# design.net
KiCad netlist of a schematic drawn in Altium Designer
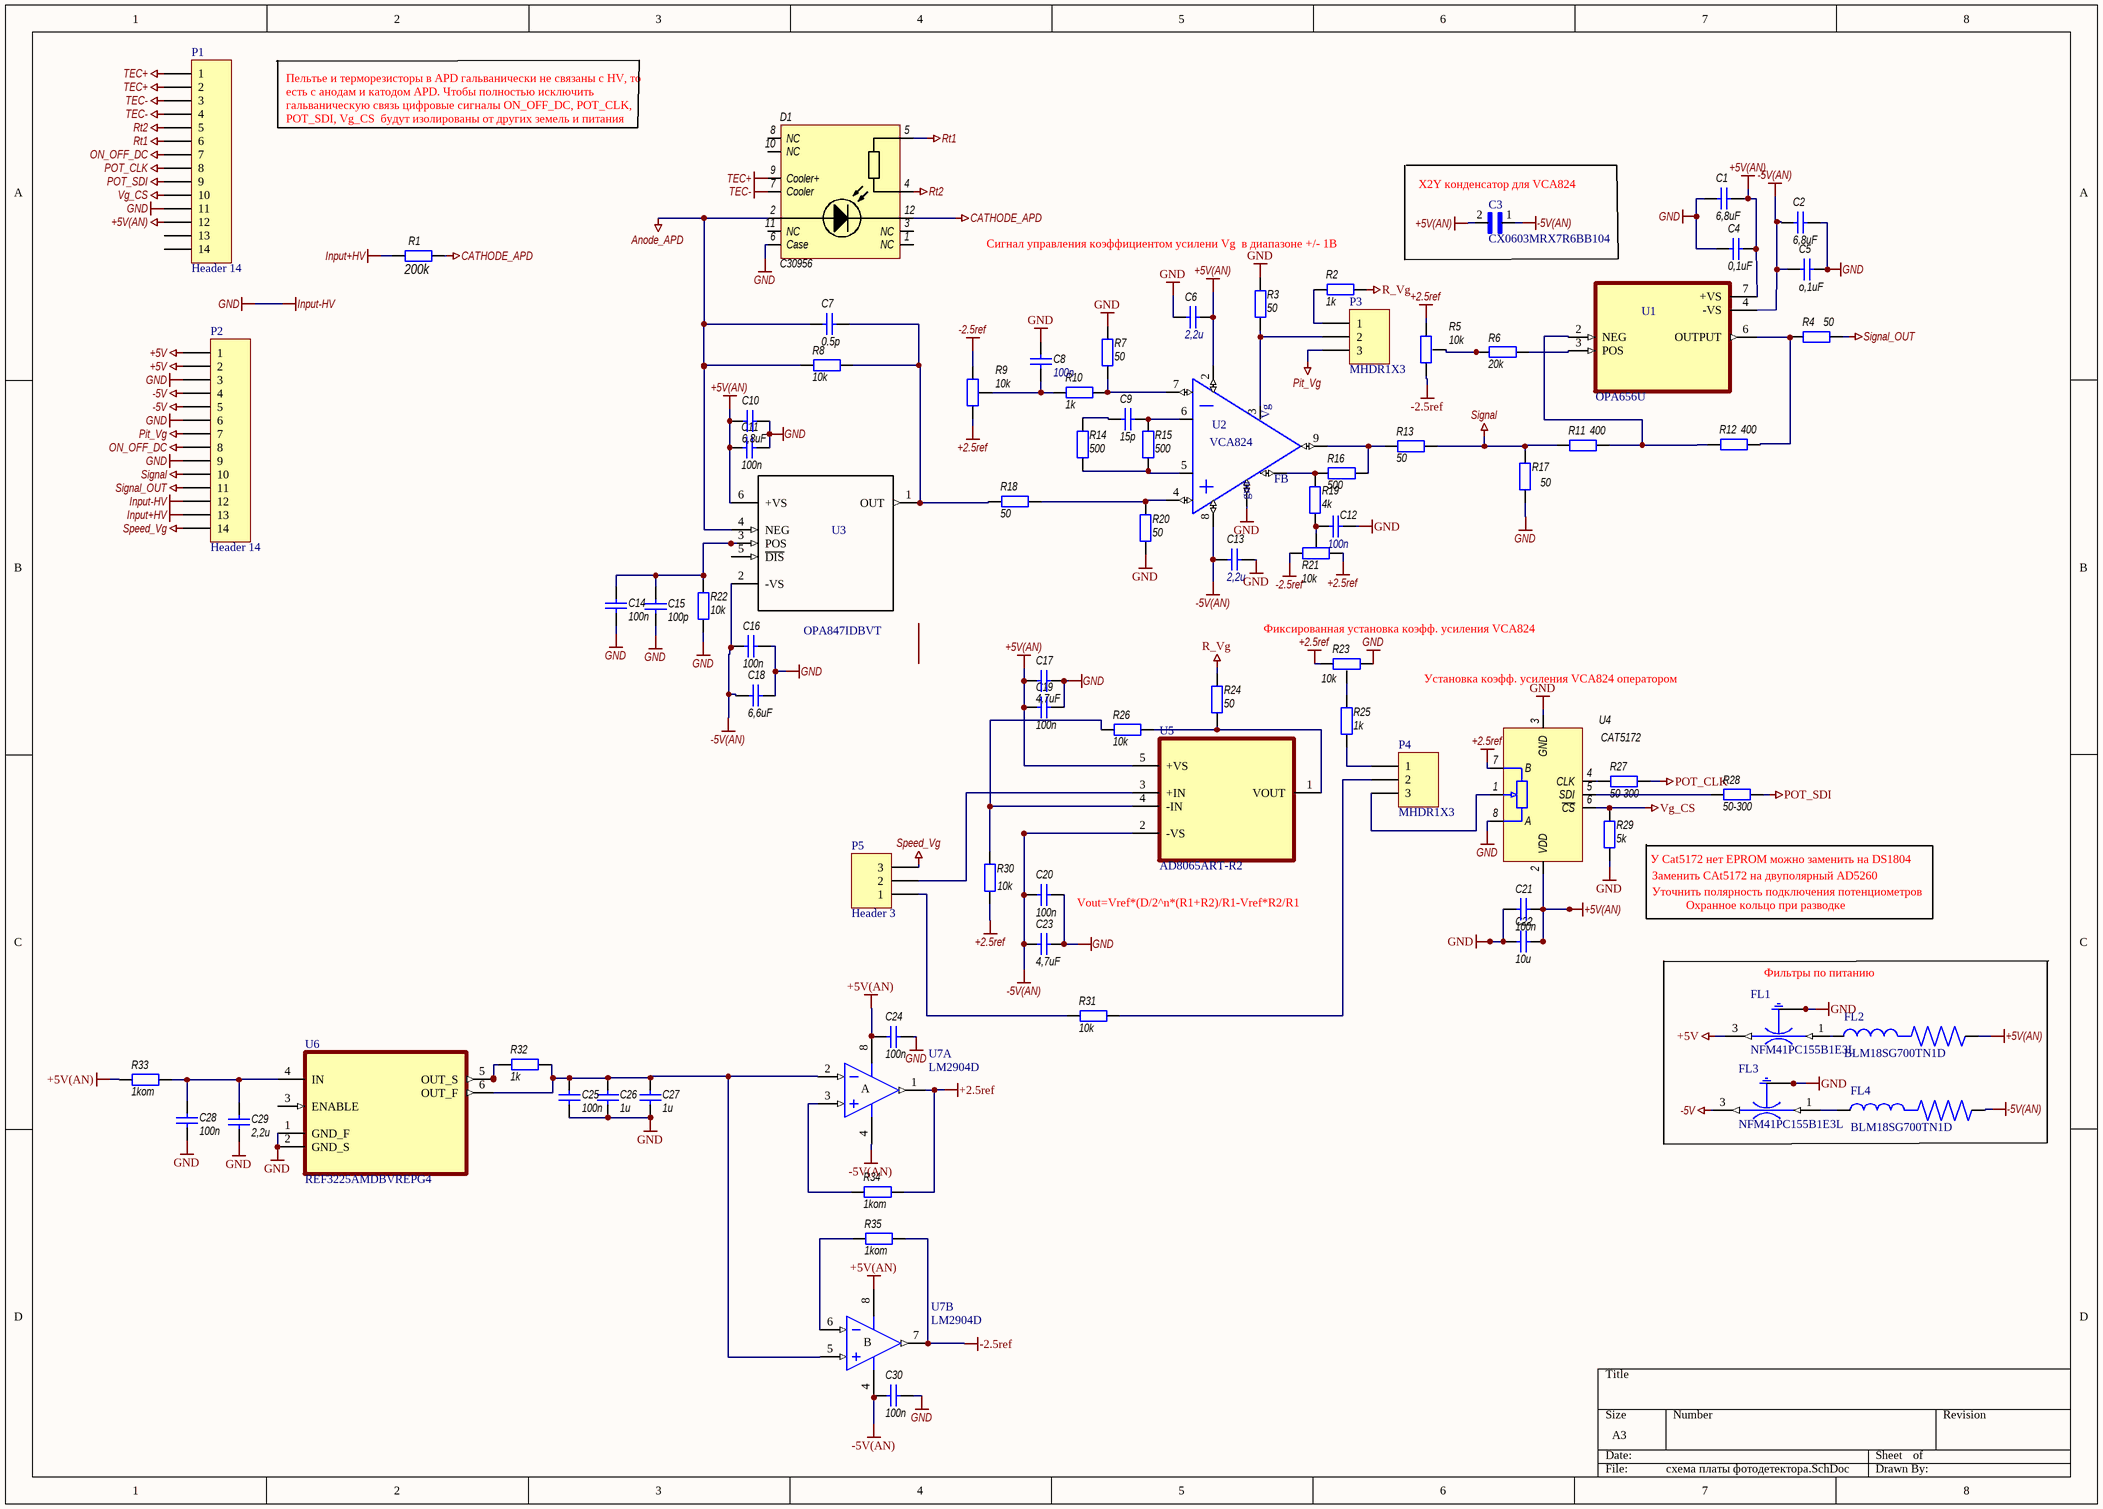
[diagram p0: схема платы фотодетектора.SchDoc]

(export (version "E")
  (design (tool "Eeschema 10.0.6"))
  (components
    (comp (ref "C1") (value "6,8uF") (footprint "0603") (libsource (lib "my-lib") (part "_capacitor")))
    (comp (ref "C2") (value "6,8uF") (footprint "0603") (libsource (lib "my-lib") (part "_capacitor")))
    (comp (ref "C3")
      (value "CX0603MRX7R6BB104")
      (footprint "CAPC1608X90")
      (description "0.1ÂµF Â±20% 10V Ceramic Capacitor X7R 0603 (1608 Metric)")
      (fields (field (name "MF") "Yageo"))
      (libsource (lib "CX0603MRX7R6BB104") (part "CX0603MRX7R6BB104"))
    )
    (comp (ref "C4") (value "0,1uF") (footprint "0603") (libsource (lib "my-lib") (part "_capacitor")))
    (comp (ref "C5") (value "o,1uF") (footprint "0603") (libsource (lib "my-lib") (part "_capacitor")))
    (comp (ref "C6") (value "2,2u") (footprint "0603") (libsource (lib "my-lib") (part "_capacitor")))
    (comp (ref "C7") (value "0.5p") (footprint "0603") (libsource (lib "my-lib") (part "_capacitor")))
    (comp (ref "C8") (value "100n") (footprint "0603") (libsource (lib "my-lib") (part "_capacitor")))
    (comp (ref "C9") (value "15p") (footprint "0603") (libsource (lib "my-lib") (part "_capacitor")))
    (comp (ref "C10") (value "6,8uF") (footprint "0603") (libsource (lib "my-lib") (part "_capacitor")))
    (comp (ref "C11") (value "100n") (footprint "0603") (libsource (lib "my-lib") (part "_capacitor")))
    (comp (ref "C12") (value "100n") (footprint "0603") (libsource (lib "my-lib") (part "_capacitor")))
    (comp (ref "C13") (value "2,2u") (footprint "0603") (libsource (lib "my-lib") (part "_capacitor")))
    (comp (ref "C14") (value "100n") (footprint "0603") (libsource (lib "my-lib") (part "_capacitor")))
    (comp (ref "C15") (value "100p") (footprint "0603") (libsource (lib "my-lib") (part "_capacitor")))
    (comp (ref "C16") (value "100n") (footprint "0603") (libsource (lib "my-lib") (part "_capacitor")))
    (comp (ref "C17") (value "4,7uF") (footprint "0603") (libsource (lib "my-lib") (part "_capacitor")))
    (comp (ref "C18") (value "6,6uF") (footprint "0603") (libsource (lib "my-lib") (part "_capacitor")))
    (comp (ref "C19") (value "100n") (footprint "0603") (libsource (lib "my-lib") (part "_capacitor")))
    (comp (ref "C20") (value "100n") (footprint "0603") (libsource (lib "my-lib") (part "_capacitor")))
    (comp (ref "C21") (value "100n") (footprint "0603") (libsource (lib "my-lib") (part "_capacitor")))
    (comp (ref "C22") (value "10u") (footprint "0603") (libsource (lib "my-lib") (part "_capacitor")))
    (comp (ref "C23") (value "4,7uF") (footprint "0603") (libsource (lib "my-lib") (part "_capacitor")))
    (comp (ref "C24") (value "100n") (footprint "0603") (libsource (lib "my-lib") (part "_capacitor")))
    (comp (ref "C25") (value "100n") (footprint "0603") (libsource (lib "my-lib") (part "_capacitor")))
    (comp (ref "C26") (value "1u") (footprint "0603") (libsource (lib "pcb2") (part "_capacitor")))
    (comp (ref "C27") (value "1u") (footprint "0603") (libsource (lib "pcb2") (part "_capacitor")))
    (comp (ref "C28") (value "100n") (footprint "0603") (libsource (lib "pcb2") (part "_capacitor")))
    (comp (ref "C29") (value "2,2u") (footprint "0603") (libsource (lib "pcb2") (part "_capacitor")))
    (comp (ref "C30") (value "100n") (footprint "0603") (libsource (lib "my-lib") (part "_capacitor")))
    (comp (ref "D1")
      (value "C30956")
      (footprint "C30659")
      (description "ADP_Diod")
      (libsource (lib "my-lib") (part "C30956"))
    )
    (comp (ref "FL1")
      (value "NFM41PC155B1E3L")
      (footprint "FIL_NFM41PC155B1E3L")
      (fields (field (name "MF") "Murata"))
      (libsource (lib "NFM41PC155B1E3L") (part "NFM41PC155B1E3L"))
    )
    (comp (ref "FL2")
      (value "BLM18SG700TN1D")
      (footprint "BEADC2012X105N")
      (fields (field (name "MF") "Murata") (field (name "MP") "BLM21SP111SN1D"))
      (libsource (lib "BLM21SP111SN1D") (part "BLM21SP111SN1D"))
    )
    (comp (ref "FL3")
      (value "NFM41PC155B1E3L")
      (footprint "FIL_NFM41PC155B1E3L")
      (fields (field (name "MF") "Murata"))
      (libsource (lib "NFM41PC155B1E3L") (part "NFM41PC155B1E3L"))
    )
    (comp (ref "FL4")
      (value "BLM18SG700TN1D")
      (footprint "BEADC2012X105N")
      (fields (field (name "MF") "Murata") (field (name "MP") "BLM21SP111SN1D"))
      (libsource (lib "BLM21SP111SN1D") (part "BLM21SP111SN1D"))
    )
    (comp (ref "P1")
      (value "Header 14")
      (footprint "HDR1X14")
      (description "Header, 14-Pin")
      (fields (field (name "PUBLISHER") "Altium Limited"))
      (libsource (lib "Miscellaneous Connectors") (part "Header 14"))
    )
    (comp (ref "P2")
      (value "Header 14")
      (footprint "HDR1X14")
      (description "Header, 14-Pin")
      (fields (field (name "PUBLISHER") "Altium Limited"))
      (libsource (lib "Miscellaneous Connectors") (part "Header 14"))
    )
    (comp (ref "P3")
      (value "MHDR1X3")
      (footprint "HDR1X3")
      (description "Header, 3-Pin")
      (fields (field (name "PUBLISHER") "Altium Limited"))
      (libsource (lib "Miscellaneous Connectors") (part "MHDR1X3"))
    )
    (comp (ref "P4")
      (value "MHDR1X3")
      (footprint "HDR1X3")
      (description "Header, 3-Pin")
      (fields (field (name "PUBLISHER") "Altium Limited"))
      (libsource (lib "Miscellaneous Connectors") (part "MHDR1X3"))
    )
    (comp (ref "P5")
      (value "Header 3")
      (footprint "HDR1X3")
      (description "Header, 3-Pin")
      (fields (field (name "PUBLISHER") "Altium Limited"))
      (libsource (lib "Miscellaneous Connectors") (part "Header 3"))
    )
    (comp (ref "R1")
      (value "200k")
      (footprint "0603")
      (fields (field (name "Comment") "CHV1206"))
      (libsource (lib "my-lib") (part "_resistor"))
    )
    (comp (ref "R2") (value "1k") (footprint "0603") (libsource (lib "my-lib") (part "_resistor")))
    (comp (ref "R3") (value "50") (footprint "0603") (libsource (lib "my-lib") (part "_resistor")))
    (comp (ref "R4") (value "50") (footprint "0603") (libsource (lib "my-lib") (part "_resistor")))
    (comp (ref "R5")
      (value "10k")
      (footprint "respotBourns")
      (description "3224J-1-103")
      (libsource (lib "my-lib") (part "_resistor_pot"))
    )
    (comp (ref "R6") (value "20k") (footprint "0603") (libsource (lib "my-lib") (part "_resistor")))
    (comp (ref "R7") (value "50") (footprint "0603") (libsource (lib "my-lib") (part "_resistor")))
    (comp (ref "R8") (value "10k") (footprint "0603") (libsource (lib "my-lib") (part "_resistor")))
    (comp (ref "R9")
      (value "10k")
      (footprint "respotBourns")
      (description "3224J-1-103")
      (libsource (lib "my-lib") (part "_resistor_pot"))
    )
    (comp (ref "R10") (value "1k") (footprint "0603") (libsource (lib "my-lib") (part "_resistor")))
    (comp (ref "R11") (value "400") (footprint "0603") (libsource (lib "my-lib") (part "_resistor")))
    (comp (ref "R12") (value "400") (footprint "0603") (libsource (lib "my-lib") (part "_resistor")))
    (comp (ref "R13") (value "50") (footprint "0603") (libsource (lib "my-lib") (part "_resistor")))
    (comp (ref "R14") (value "500") (footprint "0603") (libsource (lib "my-lib") (part "_resistor")))
    (comp (ref "R15") (value "500") (footprint "0603") (libsource (lib "my-lib") (part "_resistor")))
    (comp (ref "R16") (value "500") (footprint "0603") (libsource (lib "my-lib") (part "_resistor")))
    (comp (ref "R17") (value "50") (footprint "0603") (libsource (lib "my-lib") (part "_resistor")))
    (comp (ref "R18") (value "50") (footprint "0603") (libsource (lib "my-lib") (part "_resistor")))
    (comp (ref "R19") (value "4k") (footprint "0603") (libsource (lib "my-lib") (part "_resistor")))
    (comp (ref "R20") (value "50") (footprint "0603") (libsource (lib "my-lib") (part "_resistor")))
    (comp (ref "R21")
      (value "10k")
      (footprint "respotBourns")
      (description "3224J-1-103")
      (libsource (lib "my-lib") (part "_resistor_pot"))
    )
    (comp (ref "R22") (value "10k") (footprint "0603") (libsource (lib "my-lib") (part "_resistor")))
    (comp (ref "R23")
      (value "10k")
      (footprint "respotBourns")
      (description "3224j-1-103")
      (libsource (lib "my-lib") (part "_resistor_pot"))
    )
    (comp (ref "R24") (value "50") (footprint "0603") (libsource (lib "my-lib") (part "_resistor")))
    (comp (ref "R25") (value "1k") (footprint "0603") (libsource (lib "my-lib") (part "_resistor")))
    (comp (ref "R26") (value "10k") (footprint "0603") (libsource (lib "my-lib") (part "_resistor")))
    (comp (ref "R27") (value "50-300") (footprint "0603") (libsource (lib "my-lib") (part "_resistor")))
    (comp (ref "R28") (value "50-300") (footprint "0603") (libsource (lib "my-lib") (part "_resistor")))
    (comp (ref "R29") (value "5k") (footprint "0603") (libsource (lib "my-lib") (part "_resistor")))
    (comp (ref "R30") (value "10k") (footprint "0603") (libsource (lib "my-lib") (part "_resistor")))
    (comp (ref "R31") (value "10k") (footprint "0603") (libsource (lib "my-lib") (part "_resistor")))
    (comp (ref "R32") (value "1k") (footprint "0603") (libsource (lib "my-lib") (part "_resistor")))
    (comp (ref "R33") (value "1kom") (footprint "0603") (libsource (lib "pcb2") (part "_resistor")))
    (comp (ref "R34") (value "1kom") (footprint "0603") (libsource (lib "pcb2") (part "_resistor")))
    (comp (ref "R35") (value "1kom") (footprint "0603") (libsource (lib "pcb2") (part "_resistor")))
    (comp (ref "U1")
      (value "OPA656U")
      (footprint "SOIC127P599X175-8N")
      (description "Wideband, Unity Gain Stable FET-Input Operational Amplifier")
      (fields (field (name "MF") "Texas Instruments"))
      (libsource (lib "OPA656U") (part "OPA656U"))
    )
    (comp (ref "U2")
      (value "VCA824")
      (footprint "MSOP10")
      (fields (field (name "MF") "Texas Instruments"))
      (libsource (lib "VCA824") (part "VCA824"))
    )
    (comp (ref "U3")
      (value "OPA847IDBVT")
      (footprint "*SOT95P280X145-6N")
      (libsource (lib "OPA847IDBVT") (part "OPA847IDBVT"))
    )
    (comp (ref "U4")
      (value "CAT5172")
      (footprint "SOT238")
      (description "Digital potentiometr 256-position SPI")
      (libsource (lib "my-lib") (part "CAT5172"))
    )
    (comp (ref "U5")
      (value "AD8065ART-R2")
      (footprint "SOT95P290X145-5N")
      (fields (field (name "MF") "Analog Devices"))
      (libsource (lib "AD8065ART-R2") (part "AD8065ART-R2"))
    )
    (comp (ref "U6")
      (value "REF3225AMDBVREPG4")
      (footprint "SOT95P280X145-6N")
      (fields (field (name "MF") "Texas Instruments"))
      (libsource (lib "REF3225AMDBVREPG4") (part "REF3225AMDBVREPG4"))
    )
    (comp (ref "U7")
      (value "LM2904D")
      (footprint "SO8_L")
      (description "Low-Power Dual Operational Amplifier")
      (fields (field (name "PUBLISHER") "Altium Limited"))
      (libsource (lib "ST Operational Amplifier") (part "LM2904D"))
    )
  )
  (nets
    (net (code "1") (name "+2.5ref") (class "Default")
      (node (ref "R21") (pin "3") (pinfunction "3_3") (pintype "passive"))
      (node (ref "R23") (pin "3") (pinfunction "3_3") (pintype "passive"))
      (node (ref "R30") (pin "1") (pinfunction "1_1") (pintype "passive"))
      (node (ref "R34") (pin "1") (pinfunction "1_1") (pintype "passive"))
      (node (ref "R5") (pin "1") (pinfunction "1_1") (pintype "passive"))
      (node (ref "R9") (pin "3") (pinfunction "3_3") (pintype "passive"))
      (node (ref "U4") (pin "7") (pinfunction "B_7") (pintype "passive"))
      (node (ref "U7") (pin "1") (pinfunction "OUT_1") (pintype "output"))
    )
    (net (code "2") (name "+5V") (class "Default")
      (node (ref "FL1") (pin "3") (pinfunction "OUT_3") (pintype "output"))
      (node (ref "P2") (pin "1") (pinfunction "1_1") (pintype "passive"))
      (node (ref "P2") (pin "2") (pinfunction "2_2") (pintype "passive"))
    )
    (net (code "3") (name "+5V(AN)") (class "Default")
      (node (ref "C1") (pin "1") (pinfunction "1_1") (pintype "passive"))
      (node (ref "C10") (pin "1") (pinfunction "1_1") (pintype "passive"))
      (node (ref "C11") (pin "2") (pinfunction "2_2") (pintype "passive"))
      (node (ref "C17") (pin "2") (pinfunction "2_2") (pintype "passive"))
      (node (ref "C19") (pin "2") (pinfunction "2_2") (pintype "passive"))
      (node (ref "C21") (pin "2") (pinfunction "2_2") (pintype "passive"))
      (node (ref "C22") (pin "2") (pinfunction "2_2") (pintype "passive"))
      (node (ref "C24") (pin "2") (pinfunction "2_2") (pintype "passive"))
      (node (ref "C3") (pin "2") (pinfunction "2_2") (pintype "passive"))
      (node (ref "C4") (pin "1") (pinfunction "1_1") (pintype "passive"))
      (node (ref "C6") (pin "1") (pinfunction "1_1") (pintype "passive"))
      (node (ref "FL2") (pin "2") (pinfunction "2_2") (pintype "passive"))
      (node (ref "P1") (pin "12") (pinfunction "12_12") (pintype "passive"))
      (node (ref "R33") (pin "2") (pinfunction "2_2") (pintype "passive"))
      (node (ref "U1") (pin "7") (pinfunction "+VS_7") (pintype "power_in"))
      (node (ref "U2") (pin "2") (pinfunction "V+_2") (pintype "bidirectional"))
      (node (ref "U3") (pin "6") (pinfunction "+VS_6") (pintype "power_in"))
      (node (ref "U4") (pin "2") (pinfunction "VDD_2") (pintype "passive"))
      (node (ref "U5") (pin "5") (pinfunction "+VS_5") (pintype "power_in"))
      (node (ref "U7") (pin "8") (pinfunction "V+_8") (pintype "power_in"))
    )
    (net (code "4") (name "-2.5ref") (class "Default")
      (node (ref "R21") (pin "1") (pinfunction "1_1") (pintype "passive"))
      (node (ref "R35") (pin "1") (pinfunction "1_1") (pintype "passive"))
      (node (ref "R5") (pin "3") (pinfunction "3_3") (pintype "passive"))
      (node (ref "R9") (pin "1") (pinfunction "1_1") (pintype "passive"))
      (node (ref "U7") (pin "7") (pinfunction "OUT_7") (pintype "output"))
    )
    (net (code "5") (name "-5V") (class "Default")
      (node (ref "FL3") (pin "3") (pinfunction "OUT_3") (pintype "output"))
      (node (ref "P2") (pin "4") (pinfunction "4_4") (pintype "passive"))
      (node (ref "P2") (pin "5") (pinfunction "5_5") (pintype "passive"))
    )
    (net (code "6") (name "-5V(AN)") (class "Default")
      (node (ref "C13") (pin "2") (pinfunction "2_2") (pintype "passive"))
      (node (ref "C16") (pin "2") (pinfunction "2_2") (pintype "passive"))
      (node (ref "C18") (pin "1") (pinfunction "1_1") (pintype "passive"))
      (node (ref "C2") (pin "2") (pinfunction "2_2") (pintype "passive"))
      (node (ref "C20") (pin "2") (pinfunction "2_2") (pintype "passive"))
      (node (ref "C23") (pin "2") (pinfunction "2_2") (pintype "passive"))
      (node (ref "C3") (pin "1") (pinfunction "1_1") (pintype "passive"))
      (node (ref "C30") (pin "2") (pinfunction "2_2") (pintype "passive"))
      (node (ref "C5") (pin "2") (pinfunction "2_2") (pintype "passive"))
      (node (ref "FL4") (pin "2") (pinfunction "2_2") (pintype "passive"))
      (node (ref "U1") (pin "4") (pinfunction "-VS_4") (pintype "power_in"))
      (node (ref "U2") (pin "8") (pinfunction "V-_8") (pintype "bidirectional"))
      (node (ref "U3") (pin "2") (pinfunction "-VS_2") (pintype "power_in"))
      (node (ref "U5") (pin "2") (pinfunction "-VS_2") (pintype "power_in"))
      (node (ref "U7") (pin "4") (pinfunction "V-_4") (pintype "power_in"))
    )
    (net (code "7") (name "Anode_APD") (class "Default")
      (node (ref "C7") (pin "2") (pinfunction "2_2") (pintype "passive"))
      (node (ref "D1") (pin "2") (pintype "passive"))
      (node (ref "R8") (pin "1") (pinfunction "1_1") (pintype "passive"))
      (node (ref "U3") (pin "4") (pinfunction "NEG_4") (pintype "input"))
    )
    (net (code "8") (name "CATHODE_APD") (class "Default")
      (node (ref "D1") (pin "12") (pintype "passive"))
      (node (ref "R1") (pin "2") (pinfunction "2_2") (pintype "passive"))
    )
    (net (code "9") (name "GND") (class "Default")
      (node (ref "C1") (pin "2") (pinfunction "2_2") (pintype "passive"))
      (node (ref "C10") (pin "2") (pinfunction "2_2") (pintype "passive"))
      (node (ref "C11") (pin "1") (pinfunction "1_1") (pintype "passive"))
      (node (ref "C12") (pin "1") (pinfunction "1_1") (pintype "passive"))
      (node (ref "C13") (pin "1") (pinfunction "1_1") (pintype "passive"))
      (node (ref "C14") (pin "1") (pinfunction "1_1") (pintype "passive"))
      (node (ref "C15") (pin "2") (pinfunction "2_2") (pintype "passive"))
      (node (ref "C16") (pin "1") (pinfunction "1_1") (pintype "passive"))
      (node (ref "C17") (pin "1") (pinfunction "1_1") (pintype "passive"))
      (node (ref "C18") (pin "2") (pinfunction "2_2") (pintype "passive"))
      (node (ref "C19") (pin "1") (pinfunction "1_1") (pintype "passive"))
      (node (ref "C2") (pin "1") (pinfunction "1_1") (pintype "passive"))
      (node (ref "C20") (pin "1") (pinfunction "1_1") (pintype "passive"))
      (node (ref "C21") (pin "1") (pinfunction "1_1") (pintype "passive"))
      (node (ref "C22") (pin "1") (pinfunction "1_1") (pintype "passive"))
      (node (ref "C23") (pin "1") (pinfunction "1_1") (pintype "passive"))
      (node (ref "C24") (pin "1") (pinfunction "1_1") (pintype "passive"))
      (node (ref "C25") (pin "1") (pinfunction "1_1") (pintype "passive"))
      (node (ref "C26") (pin "1") (pinfunction "1_1") (pintype "passive"))
      (node (ref "C27") (pin "1") (pinfunction "1_1") (pintype "passive"))
      (node (ref "C28") (pin "1") (pinfunction "1_1") (pintype "passive"))
      (node (ref "C29") (pin "1") (pinfunction "1_1") (pintype "passive"))
      (node (ref "C30") (pin "1") (pinfunction "1_1") (pintype "passive"))
      (node (ref "C4") (pin "2") (pinfunction "2_2") (pintype "passive"))
      (node (ref "C5") (pin "1") (pinfunction "1_1") (pintype "passive"))
      (node (ref "C6") (pin "2") (pinfunction "2_2") (pintype "passive"))
      (node (ref "C8") (pin "2") (pinfunction "2_2") (pintype "passive"))
      (node (ref "D1") (pin "6") (pinfunction "Case_6") (pintype "passive"))
      (node (ref "FL1") (pin "2") (pinfunction "GND_2") (pintype "power_in"))
      (node (ref "FL1") (pin "2_1") (pinfunction "GND_2_1") (pintype "power_in"))
      (node (ref "FL1") (pin "2_3") (pinfunction "GND_2_3") (pintype "power_in"))
      (node (ref "FL1") (pin "2_4") (pinfunction "GND_2_4") (pintype "power_in"))
      (node (ref "FL3") (pin "2") (pinfunction "GND_2") (pintype "power_in"))
      (node (ref "FL3") (pin "2_1") (pinfunction "GND_2_1") (pintype "power_in"))
      (node (ref "FL3") (pin "2_3") (pinfunction "GND_2_3") (pintype "power_in"))
      (node (ref "FL3") (pin "2_4") (pinfunction "GND_2_4") (pintype "power_in"))
      (node (ref "P1") (pin "11") (pinfunction "11_11") (pintype "passive"))
      (node (ref "P2") (pin "12") (pinfunction "12_12") (pintype "passive"))
      (node (ref "P2") (pin "3") (pinfunction "3_3") (pintype "passive"))
      (node (ref "P2") (pin "6") (pinfunction "6_6") (pintype "passive"))
      (node (ref "P2") (pin "9") (pinfunction "9_9") (pintype "passive"))
      (node (ref "R17") (pin "1") (pinfunction "1_1") (pintype "passive"))
      (node (ref "R20") (pin "1") (pinfunction "1_1") (pintype "passive"))
      (node (ref "R22") (pin "2") (pinfunction "2_2") (pintype "passive"))
      (node (ref "R23") (pin "1") (pinfunction "1_1") (pintype "passive"))
      (node (ref "R29") (pin "1") (pinfunction "1_1") (pintype "passive"))
      (node (ref "R3") (pin "2") (pinfunction "2_2") (pintype "passive"))
      (node (ref "R7") (pin "2") (pinfunction "2_2") (pintype "passive"))
      (node (ref "U2") (pin "10") (pinfunction "GND_10") (pintype "bidirectional"))
      (node (ref "U4") (pin "3") (pinfunction "GND_3") (pintype "passive"))
      (node (ref "U4") (pin "8") (pinfunction "A_8") (pintype "passive"))
      (node (ref "U6") (pin "1") (pinfunction "GND_F_1") (pintype "passive"))
      (node (ref "U6") (pin "2") (pinfunction "GND_S_2") (pintype "passive"))
    )
    (net (code "10") (name "Input+HV") (class "Default")
      (node (ref "P2") (pin "13") (pinfunction "13_13") (pintype "passive"))
      (node (ref "R1") (pin "1") (pinfunction "1_1") (pintype "passive"))
    )
    (net (code "11") (name "Net-(C8-Pad1)") (class "Default")
      (node (ref "C8") (pin "1") (pinfunction "1_1") (pintype "passive"))
      (node (ref "R10") (pin "1") (pinfunction "1_1") (pintype "passive"))
      (node (ref "R9") (pin "2") (pinfunction "2_2") (pintype "passive"))
    )
    (net (code "12") (name "Net-(C9-Pad2)") (class "Default")
      (node (ref "C9") (pin "2") (pinfunction "2_2") (pintype "passive"))
      (node (ref "R14") (pin "2") (pinfunction "2_2") (pintype "passive"))
    )
    (net (code "13") (name "Net-(C12-Pad2)") (class "Default")
      (node (ref "C12") (pin "2") (pinfunction "2_2") (pintype "passive"))
      (node (ref "R19") (pin "1") (pinfunction "1_1") (pintype "passive"))
      (node (ref "R21") (pin "2") (pinfunction "2_2") (pintype "passive"))
    )
    (net (code "14") (name "Net-(FL1-IN)") (class "Default")
      (node (ref "FL1") (pin "1") (pinfunction "IN_1") (pintype "input"))
      (node (ref "FL2") (pin "1") (pinfunction "1_1") (pintype "passive"))
    )
    (net (code "15") (name "Net-(FL3-IN)") (class "Default")
      (node (ref "FL3") (pin "1") (pinfunction "IN_1") (pintype "input"))
      (node (ref "FL4") (pin "1") (pinfunction "1_1") (pintype "passive"))
    )
    (net (code "16") (name "Net-(P3-Pad1)") (class "Default")
      (node (ref "P3") (pin "1") (pinfunction "1_1") (pintype "passive"))
      (node (ref "R2") (pin "1") (pinfunction "1_1") (pintype "passive"))
    )
    (net (code "17") (name "Net-(P4-Pad1)") (class "Default")
      (node (ref "P4") (pin "1") (pinfunction "1_1") (pintype "passive"))
      (node (ref "R25") (pin "1") (pinfunction "1_1") (pintype "passive"))
    )
    (net (code "18") (name "Net-(P4-Pad2)") (class "Default")
      (node (ref "P4") (pin "2") (pinfunction "2_2") (pintype "passive"))
      (node (ref "R31") (pin "2") (pinfunction "2_2") (pintype "passive"))
    )
    (net (code "19") (name "Net-(P4-Pad3)") (class "Default")
      (node (ref "P4") (pin "3") (pinfunction "3_3") (pintype "passive"))
      (node (ref "U4") (pin "1") (pintype "passive"))
    )
    (net (code "20") (name "Net-(P5-Pad1)") (class "Default")
      (node (ref "P5") (pin "1") (pinfunction "1_1") (pintype "passive"))
      (node (ref "R31") (pin "1") (pinfunction "1_1") (pintype "passive"))
    )
    (net (code "21") (name "Net-(R5-Pad2)") (class "Default")
      (node (ref "R5") (pin "2") (pinfunction "2_2") (pintype "passive"))
      (node (ref "R6") (pin "1") (pinfunction "1_1") (pintype "passive"))
    )
    (net (code "22") (name "Net-(R23-Pad2)") (class "Default")
      (node (ref "R23") (pin "2") (pinfunction "2_2") (pintype "passive"))
      (node (ref "R25") (pin "2") (pinfunction "2_2") (pintype "passive"))
    )
    (net (code "23") (name "Net-(U1-NEG)") (class "Default")
      (node (ref "R11") (pin "2") (pinfunction "2_2") (pintype "passive"))
      (node (ref "R12") (pin "1") (pinfunction "1_1") (pintype "passive"))
      (node (ref "U1") (pin "2") (pinfunction "NEG_2") (pintype "input"))
    )
    (net (code "24") (name "Net-(U1-OUTPUT)") (class "Default")
      (node (ref "R12") (pin "2") (pinfunction "2_2") (pintype "passive"))
      (node (ref "R4") (pin "1") (pinfunction "1_1") (pintype "passive"))
      (node (ref "U1") (pin "6") (pinfunction "OUTPUT_6") (pintype "output"))
    )
    (net (code "25") (name "Net-(U1-POS)") (class "Default")
      (node (ref "R6") (pin "2") (pinfunction "2_2") (pintype "passive"))
      (node (ref "U1") (pin "3") (pinfunction "POS_3") (pintype "input"))
    )
    (net (code "26") (name "Net-(U2-FB)") (class "Default")
      (node (ref "R16") (pin "1") (pinfunction "1_1") (pintype "passive"))
      (node (ref "R19") (pin "2") (pinfunction "2_2") (pintype "passive"))
      (node (ref "U2") (pin "1") (pinfunction "FB_1") (pintype "bidirectional"))
    )
    (net (code "27") (name "Net-(U2-IN+)") (class "Default")
      (node (ref "R18") (pin "2") (pinfunction "2_2") (pintype "passive"))
      (node (ref "R20") (pin "2") (pinfunction "2_2") (pintype "passive"))
      (node (ref "U2") (pin "4") (pinfunction "IN+_4") (pintype "bidirectional"))
    )
    (net (code "28") (name "Net-(U2-IN-)") (class "Default")
      (node (ref "R10") (pin "2") (pinfunction "2_2") (pintype "passive"))
      (node (ref "R7") (pin "1") (pinfunction "1_1") (pintype "passive"))
      (node (ref "U2") (pin "7") (pinfunction "IN-_7") (pintype "bidirectional"))
    )
    (net (code "29") (name "Net-(U2-OUT)") (class "Default")
      (node (ref "R13") (pin "1") (pinfunction "1_1") (pintype "passive"))
      (node (ref "R16") (pin "2") (pinfunction "2_2") (pintype "passive"))
      (node (ref "U2") (pin "9") (pinfunction "OUT_9") (pintype "bidirectional"))
    )
    (net (code "30") (name "Net-(U2-RG+)") (class "Default")
      (node (ref "R14") (pin "1") (pinfunction "1_1") (pintype "passive"))
      (node (ref "R15") (pin "1") (pinfunction "1_1") (pintype "passive"))
      (node (ref "U2") (pin "5") (pinfunction "RG+_5") (pintype "bidirectional"))
    )
    (net (code "31") (name "Net-(U2-RG-)") (class "Default")
      (node (ref "C9") (pin "1") (pinfunction "1_1") (pintype "passive"))
      (node (ref "R15") (pin "2") (pinfunction "2_2") (pintype "passive"))
      (node (ref "U2") (pin "6") (pinfunction "RG-_6") (pintype "bidirectional"))
    )
    (net (code "32") (name "Net-(U2-VG)") (class "Default")
      (node (ref "P3") (pin "2") (pinfunction "2_2") (pintype "passive"))
      (node (ref "R3") (pin "1") (pinfunction "1_1") (pintype "passive"))
      (node (ref "U2") (pin "3") (pinfunction "VG_3") (pintype "bidirectional"))
    )
    (net (code "33") (name "Net-(U3-OUT)") (class "Default")
      (node (ref "C7") (pin "1") (pinfunction "1_1") (pintype "passive"))
      (node (ref "R18") (pin "1") (pinfunction "1_1") (pintype "passive"))
      (node (ref "R8") (pin "2") (pinfunction "2_2") (pintype "passive"))
      (node (ref "U3") (pin "1") (pinfunction "OUT_1") (pintype "output"))
    )
    (net (code "34") (name "Net-(U3-POS)") (class "Default")
      (node (ref "C14") (pin "2") (pinfunction "2_2") (pintype "passive"))
      (node (ref "C15") (pin "1") (pinfunction "1_1") (pintype "passive"))
      (node (ref "R22") (pin "1") (pinfunction "1_1") (pintype "passive"))
      (node (ref "U3") (pin "3") (pinfunction "POS_3") (pintype "input"))
    )
    (net (code "35") (name "Net-(U4-CLK)") (class "Default")
      (node (ref "R27") (pin "1") (pinfunction "1_1") (pintype "passive"))
      (node (ref "U4") (pin "4") (pinfunction "CLK_4") (pintype "passive"))
    )
    (net (code "36") (name "Net-(U4-SDI)") (class "Default")
      (node (ref "R28") (pin "1") (pinfunction "1_1") (pintype "passive"))
      (node (ref "U4") (pin "5") (pinfunction "SDI_5") (pintype "passive"))
    )
    (net (code "37") (name "Net-(U5-+IN)") (class "Default")
      (node (ref "P5") (pin "2") (pinfunction "2_2") (pintype "passive"))
      (node (ref "U5") (pin "3") (pinfunction "+IN_3") (pintype "passive"))
    )
    (net (code "38") (name "Net-(U5--IN)") (class "Default")
      (node (ref "R26") (pin "1") (pinfunction "1_1") (pintype "passive"))
      (node (ref "R30") (pin "2") (pinfunction "2_2") (pintype "passive"))
      (node (ref "U5") (pin "4") (pinfunction "-IN_4") (pintype "passive"))
    )
    (net (code "39") (name "Net-(U5-VOUT)") (class "Default")
      (node (ref "R24") (pin "1") (pinfunction "1_1") (pintype "passive"))
      (node (ref "R26") (pin "2") (pinfunction "2_2") (pintype "passive"))
      (node (ref "U5") (pin "1") (pinfunction "VOUT_1") (pintype "passive"))
    )
    (net (code "40") (name "Net-(U6-IN)") (class "Default")
      (node (ref "C28") (pin "2") (pinfunction "2_2") (pintype "passive"))
      (node (ref "C29") (pin "2") (pinfunction "2_2") (pintype "passive"))
      (node (ref "R33") (pin "1") (pinfunction "1_1") (pintype "passive"))
      (node (ref "U6") (pin "4") (pinfunction "IN_4") (pintype "power_in"))
    )
    (net (code "41") (name "Net-(U6-OUT_F)") (class "Default")
      (node (ref "C25") (pin "2") (pinfunction "2_2") (pintype "passive"))
      (node (ref "C26") (pin "2") (pinfunction "2_2") (pintype "passive"))
      (node (ref "C27") (pin "2") (pinfunction "2_2") (pintype "passive"))
      (node (ref "R32") (pin "2") (pinfunction "2_2") (pintype "passive"))
      (node (ref "U6") (pin "6") (pinfunction "OUT_F_6") (pintype "output"))
      (node (ref "U7") (pin "2") (pinfunction "IN-_2") (pintype "input"))
      (node (ref "U7") (pin "5") (pinfunction "IN+_5") (pintype "input"))
    )
    (net (code "42") (name "Net-(U6-OUT_S)") (class "Default")
      (node (ref "R32") (pin "1") (pinfunction "1_1") (pintype "passive"))
      (node (ref "U6") (pin "5") (pinfunction "OUT_S_5") (pintype "output"))
    )
    (net (code "43") (name "Net-(U7A-IN+)") (class "Default")
      (node (ref "R34") (pin "2") (pinfunction "2_2") (pintype "passive"))
      (node (ref "U7") (pin "3") (pinfunction "IN+_3") (pintype "input"))
    )
    (net (code "44") (name "Net-(U7B-IN-)") (class "Default")
      (node (ref "R35") (pin "2") (pinfunction "2_2") (pintype "passive"))
      (node (ref "U7") (pin "6") (pinfunction "IN-_6") (pintype "input"))
    )
    (net (code "45") (name "ON_OFF_DC") (class "Default")
      (node (ref "P1") (pin "7") (pinfunction "7_7") (pintype "passive"))
      (node (ref "P2") (pin "8") (pinfunction "8_8") (pintype "passive"))
    )
    (net (code "46") (name "POT_CLK") (class "Default")
      (node (ref "P1") (pin "8") (pinfunction "8_8") (pintype "passive"))
      (node (ref "R27") (pin "2") (pinfunction "2_2") (pintype "passive"))
    )
    (net (code "47") (name "POT_SDI") (class "Default")
      (node (ref "P1") (pin "9") (pinfunction "9_9") (pintype "passive"))
      (node (ref "R28") (pin "2") (pinfunction "2_2") (pintype "passive"))
    )
    (net (code "48") (name "Pit_Vg") (class "Default")
      (node (ref "P2") (pin "7") (pinfunction "7_7") (pintype "passive"))
      (node (ref "P3") (pin "3") (pinfunction "3_3") (pintype "passive"))
    )
    (net (code "49") (name "R_Vg") (class "Default")
      (node (ref "R2") (pin "2") (pinfunction "2_2") (pintype "passive"))
      (node (ref "R24") (pin "2") (pinfunction "2_2") (pintype "passive"))
    )
    (net (code "50") (name "Rt1") (class "Default")
      (node (ref "D1") (pin "5") (pintype "passive"))
      (node (ref "P1") (pin "6") (pinfunction "6_6") (pintype "passive"))
    )
    (net (code "51") (name "Rt2") (class "Default")
      (node (ref "D1") (pin "4") (pintype "passive"))
      (node (ref "P1") (pin "5") (pinfunction "5_5") (pintype "passive"))
    )
    (net (code "52") (name "Signal") (class "Default")
      (node (ref "P2") (pin "10") (pinfunction "10_10") (pintype "passive"))
      (node (ref "R11") (pin "1") (pinfunction "1_1") (pintype "passive"))
      (node (ref "R13") (pin "2") (pinfunction "2_2") (pintype "passive"))
      (node (ref "R17") (pin "2") (pinfunction "2_2") (pintype "passive"))
    )
    (net (code "53") (name "Signal_OUT") (class "Default")
      (node (ref "P2") (pin "11") (pinfunction "11_11") (pintype "passive"))
      (node (ref "R4") (pin "2") (pinfunction "2_2") (pintype "passive"))
    )
    (net (code "54") (name "Speed_Vg") (class "Default")
      (node (ref "P2") (pin "14") (pinfunction "14_14") (pintype "passive"))
      (node (ref "P5") (pin "3") (pinfunction "3_3") (pintype "passive"))
    )
    (net (code "55") (name "TEC+") (class "Default")
      (node (ref "D1") (pin "9") (pinfunction "Cooler+_9") (pintype "passive"))
      (node (ref "P1") (pin "1") (pinfunction "1_1") (pintype "passive"))
      (node (ref "P1") (pin "2") (pinfunction "2_2") (pintype "passive"))
    )
    (net (code "56") (name "TEC-") (class "Default")
      (node (ref "D1") (pin "7") (pinfunction "Cooler_7") (pintype "passive"))
      (node (ref "P1") (pin "3") (pinfunction "3_3") (pintype "passive"))
      (node (ref "P1") (pin "4") (pinfunction "4_4") (pintype "passive"))
    )
    (net (code "57") (name "Vg_CS") (class "Default")
      (node (ref "P1") (pin "10") (pinfunction "10_10") (pintype "passive"))
      (node (ref "R29") (pin "2") (pinfunction "2_2") (pintype "passive"))
      (node (ref "U4") (pin "6") (pinfunction "~{CS}_6") (pintype "passive"))
    )
    (net (code "58") (name "unconnected-(D1-NC-Pad1)") (class "Default")
      (node (ref "D1") (pin "1") (pinfunction "NC_1") (pintype "passive"))
    )
    (net (code "59") (name "unconnected-(D1-NC-Pad3)") (class "Default")
      (node (ref "D1") (pin "3") (pinfunction "NC_3") (pintype "passive"))
    )
    (net (code "60") (name "unconnected-(D1-NC-Pad8)") (class "Default")
      (node (ref "D1") (pin "8") (pinfunction "NC_8") (pintype "passive"))
    )
    (net (code "61") (name "unconnected-(D1-NC-Pad10)") (class "Default")
      (node (ref "D1") (pin "10") (pinfunction "NC_10") (pintype "passive"))
    )
    (net (code "62") (name "unconnected-(D1-NC-Pad11)") (class "Default")
      (node (ref "D1") (pin "11") (pinfunction "NC_11") (pintype "passive"))
    )
    (net (code "63") (name "unconnected-(P1-Pad13)") (class "Default")
      (node (ref "P1") (pin "13") (pinfunction "13_13") (pintype "passive"))
    )
    (net (code "64") (name "unconnected-(P1-Pad14)") (class "Default")
      (node (ref "P1") (pin "14") (pinfunction "14_14") (pintype "passive"))
    )
    (net (code "65") (name "unconnected-(U3-~{DIS}-Pad5)") (class "Default")
      (node (ref "U3") (pin "5") (pinfunction "~{DIS}_5") (pintype "input"))
    )
    (net (code "66") (name "unconnected-(U6-ENABLE-Pad3)") (class "Default")
      (node (ref "U6") (pin "3") (pinfunction "ENABLE_3") (pintype "input"))
    )
  )
)
